# Busboard_expand_v12.net
KiCad netlist of a schematic drawn in EAGLE
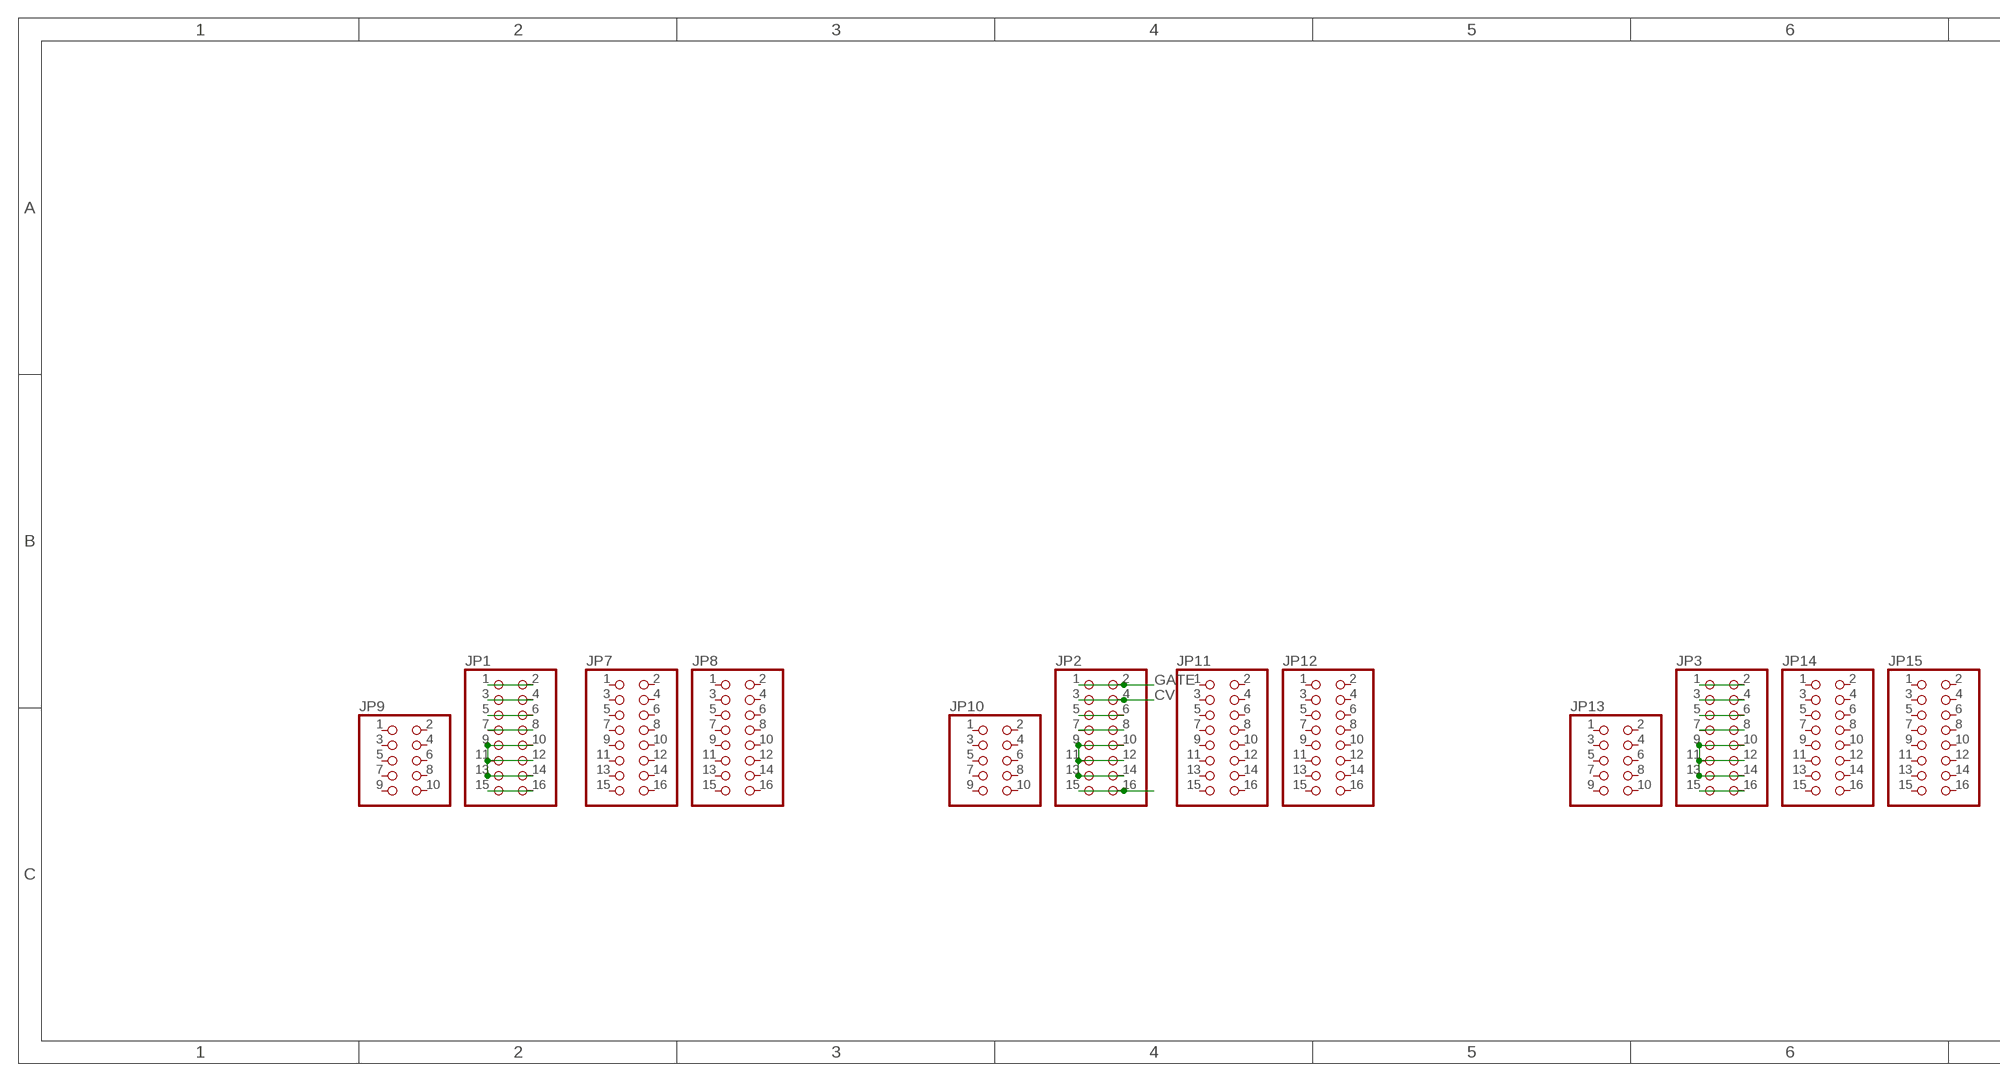
[diagram p0: schematic, sheet 1, part 1 of 2]
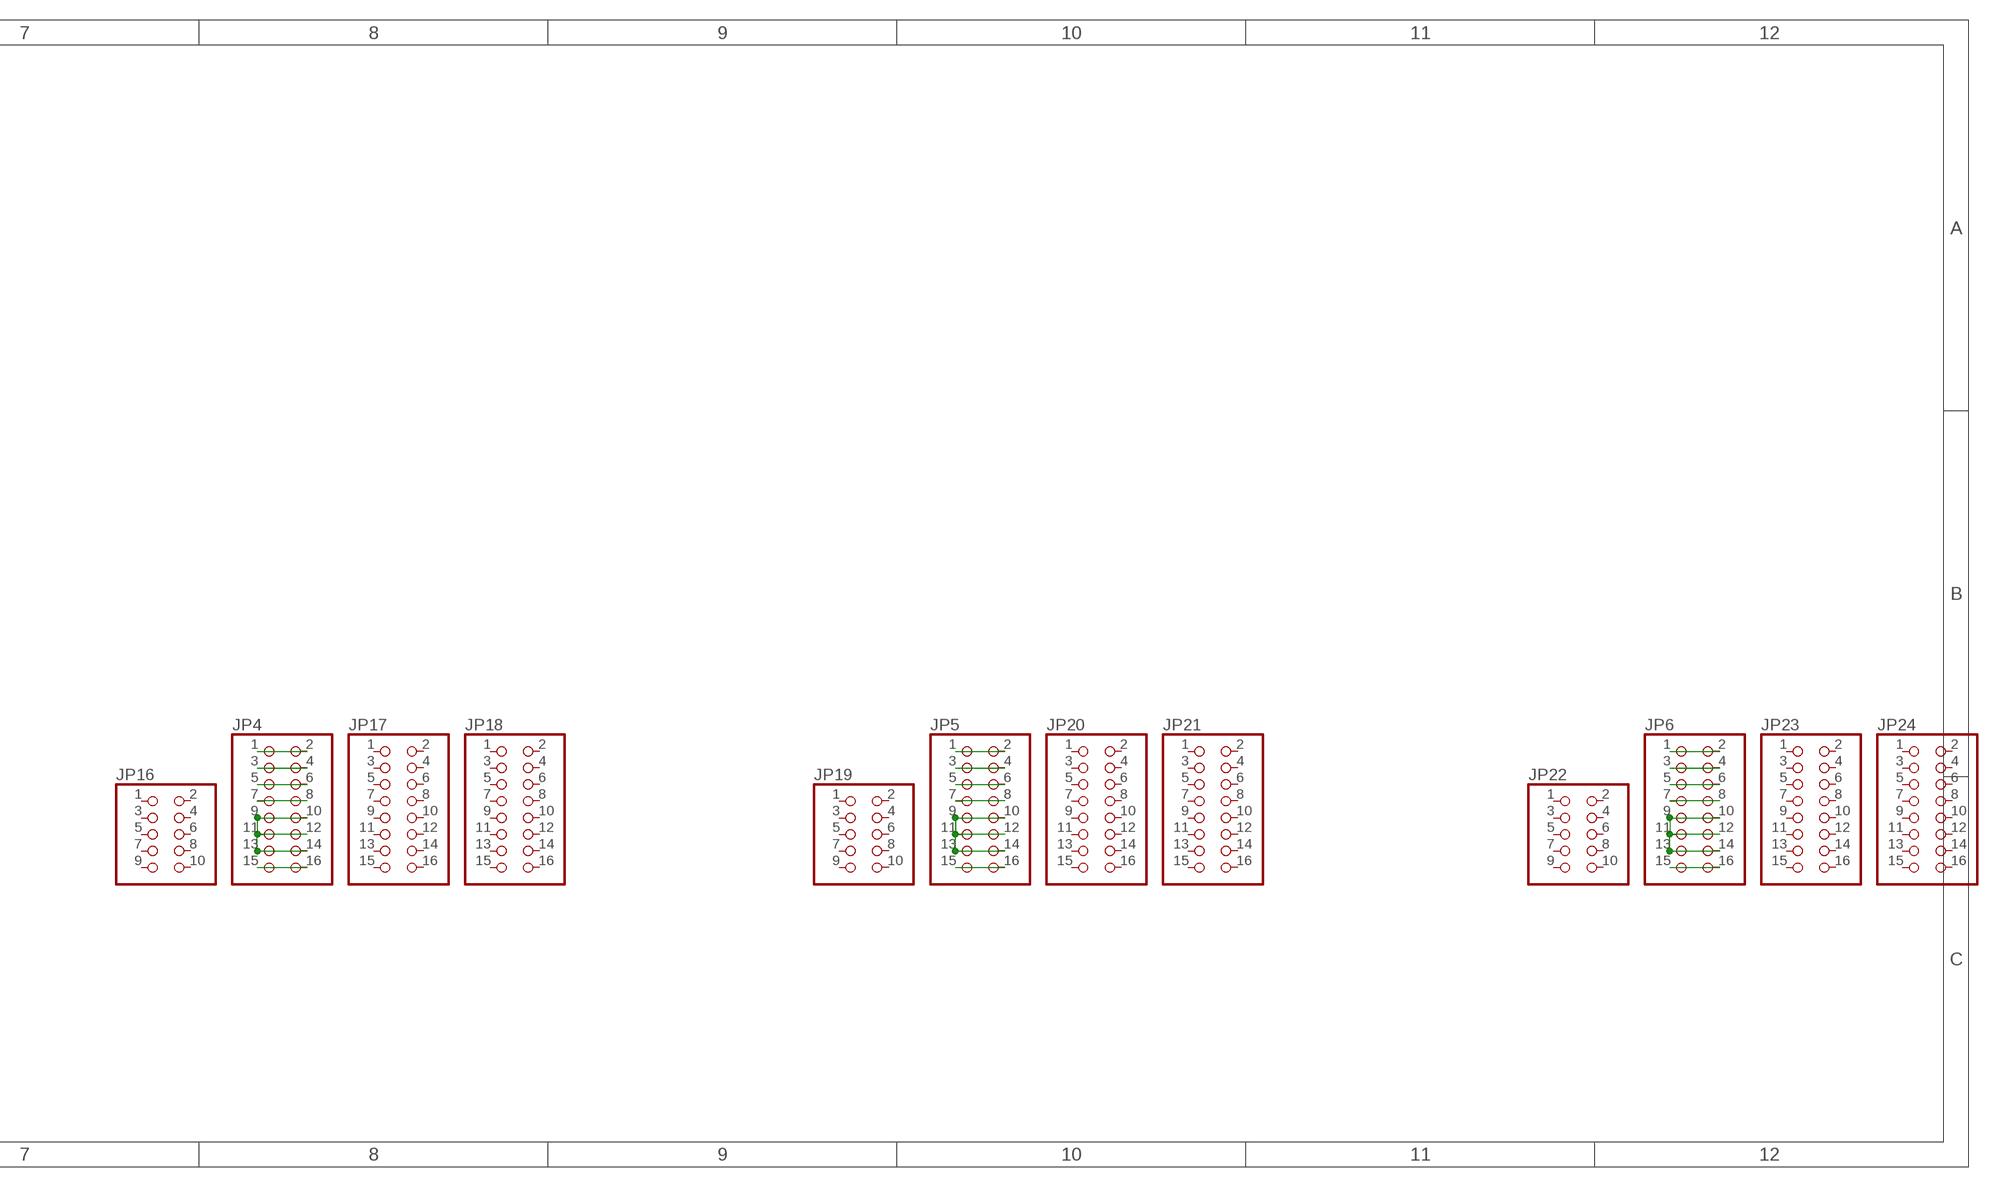
[diagram p1: schematic, sheet 1, part 2 of 2]

(export (version "E")
  (design (tool "Eeschema 10.0.6"))
  (components
    (comp (ref "JP1")
      (value "PINHD-2X8")
      (footprint "eagle-import:2X08")
      (libsource (lib "eagle-import") (part "PINHD-2X8"))
    )
    (comp (ref "JP2")
      (value "PINHD-2X8")
      (footprint "eagle-import:2X08")
      (libsource (lib "eagle-import") (part "PINHD-2X8"))
    )
    (comp (ref "JP3")
      (value "PINHD-2X8")
      (footprint "eagle-import:2X08")
      (libsource (lib "eagle-import") (part "PINHD-2X8"))
    )
    (comp (ref "JP4")
      (value "PINHD-2X8")
      (footprint "eagle-import:2X08")
      (libsource (lib "eagle-import") (part "PINHD-2X8"))
    )
    (comp (ref "JP5")
      (value "PINHD-2X8")
      (footprint "eagle-import:2X08")
      (libsource (lib "eagle-import") (part "PINHD-2X8"))
    )
    (comp (ref "JP6")
      (value "PINHD-2X8")
      (footprint "eagle-import:2X08")
      (libsource (lib "eagle-import") (part "PINHD-2X8"))
    )
    (comp (ref "JP7")
      (value "PINHD-2X8/90")
      (footprint "eagle-import:2X08_90")
      (libsource (lib "eagle-import") (part "pinhead_325_PINHD-2X8/90"))
    )
    (comp (ref "JP8")
      (value "PINHD-2X8/90")
      (footprint "eagle-import:2X08_90")
      (libsource (lib "eagle-import") (part "pinhead_325_PINHD-2X8/90"))
    )
    (comp (ref "JP9")
      (value "PINHD-2X5")
      (footprint "eagle-import:2X05")
      (libsource (lib "eagle-import") (part "PINHD-2X5"))
    )
    (comp (ref "JP10")
      (value "PINHD-2X5")
      (footprint "eagle-import:2X05")
      (libsource (lib "eagle-import") (part "PINHD-2X5"))
    )
    (comp (ref "JP11")
      (value "PINHD-2X8/90")
      (footprint "eagle-import:2X08_90")
      (libsource (lib "eagle-import") (part "pinhead_325_PINHD-2X8/90"))
    )
    (comp (ref "JP12")
      (value "PINHD-2X8/90")
      (footprint "eagle-import:2X08_90")
      (libsource (lib "eagle-import") (part "pinhead_325_PINHD-2X8/90"))
    )
    (comp (ref "JP13")
      (value "PINHD-2X5")
      (footprint "eagle-import:2X05")
      (libsource (lib "eagle-import") (part "PINHD-2X5"))
    )
    (comp (ref "JP14")
      (value "PINHD-2X8/90")
      (footprint "eagle-import:2X08_90")
      (libsource (lib "eagle-import") (part "pinhead_325_PINHD-2X8/90"))
    )
    (comp (ref "JP15")
      (value "PINHD-2X8/90")
      (footprint "eagle-import:2X08_90")
      (libsource (lib "eagle-import") (part "pinhead_325_PINHD-2X8/90"))
    )
    (comp (ref "JP16")
      (value "PINHD-2X5")
      (footprint "eagle-import:2X05")
      (libsource (lib "eagle-import") (part "PINHD-2X5"))
    )
    (comp (ref "JP17")
      (value "PINHD-2X8/90")
      (footprint "eagle-import:2X08_90")
      (libsource (lib "eagle-import") (part "pinhead_325_PINHD-2X8/90"))
    )
    (comp (ref "JP18")
      (value "PINHD-2X8/90")
      (footprint "eagle-import:2X08_90")
      (libsource (lib "eagle-import") (part "pinhead_325_PINHD-2X8/90"))
    )
    (comp (ref "JP19")
      (value "PINHD-2X5")
      (footprint "eagle-import:2X05")
      (libsource (lib "eagle-import") (part "PINHD-2X5"))
    )
    (comp (ref "JP20")
      (value "PINHD-2X8/90")
      (footprint "eagle-import:2X08_90")
      (libsource (lib "eagle-import") (part "pinhead_325_PINHD-2X8/90"))
    )
    (comp (ref "JP21")
      (value "PINHD-2X8/90")
      (footprint "eagle-import:2X08_90")
      (libsource (lib "eagle-import") (part "pinhead_325_PINHD-2X8/90"))
    )
    (comp (ref "JP22")
      (value "PINHD-2X5")
      (footprint "eagle-import:2X05")
      (libsource (lib "eagle-import") (part "PINHD-2X5"))
    )
    (comp (ref "JP23")
      (value "PINHD-2X8/90")
      (footprint "eagle-import:2X08_90")
      (libsource (lib "eagle-import") (part "pinhead_325_PINHD-2X8/90"))
    )
    (comp (ref "JP24")
      (value "PINHD-2X8/90")
      (footprint "eagle-import:2X08_90")
      (libsource (lib "eagle-import") (part "pinhead_325_PINHD-2X8/90"))
    )
  )
  (nets
    (net (code "1") (name "/CV") (class "Default")
      (node (ref "JP1") (pin "3") (pinfunction "3_3") (pintype "passive"))
      (node (ref "JP1") (pin "4") (pinfunction "4_4") (pintype "passive"))
      (node (ref "JP2") (pin "3") (pinfunction "3_3") (pintype "passive"))
      (node (ref "JP2") (pin "4") (pinfunction "4_4") (pintype "passive"))
      (node (ref "JP3") (pin "3") (pinfunction "3_3") (pintype "passive"))
      (node (ref "JP3") (pin "4") (pinfunction "4_4") (pintype "passive"))
      (node (ref "JP4") (pin "3") (pinfunction "3_3") (pintype "passive"))
      (node (ref "JP4") (pin "4") (pinfunction "4_4") (pintype "passive"))
      (node (ref "JP5") (pin "3") (pinfunction "3_3") (pintype "passive"))
      (node (ref "JP5") (pin "4") (pinfunction "4_4") (pintype "passive"))
      (node (ref "JP6") (pin "3") (pinfunction "3_3") (pintype "passive"))
      (node (ref "JP6") (pin "4") (pinfunction "4_4") (pintype "passive"))
    )
    (net (code "2") (name "/GATE") (class "Default")
      (node (ref "JP1") (pin "1") (pinfunction "1_1") (pintype "passive"))
      (node (ref "JP1") (pin "2") (pinfunction "2_2") (pintype "passive"))
      (node (ref "JP2") (pin "1") (pinfunction "1_1") (pintype "passive"))
      (node (ref "JP2") (pin "2") (pinfunction "2_2") (pintype "passive"))
      (node (ref "JP3") (pin "1") (pinfunction "1_1") (pintype "passive"))
      (node (ref "JP3") (pin "2") (pinfunction "2_2") (pintype "passive"))
      (node (ref "JP4") (pin "1") (pinfunction "1_1") (pintype "passive"))
      (node (ref "JP4") (pin "2") (pinfunction "2_2") (pintype "passive"))
      (node (ref "JP5") (pin "1") (pinfunction "1_1") (pintype "passive"))
      (node (ref "JP5") (pin "2") (pinfunction "2_2") (pintype "passive"))
      (node (ref "JP6") (pin "1") (pinfunction "1_1") (pintype "passive"))
      (node (ref "JP6") (pin "2") (pinfunction "2_2") (pintype "passive"))
    )
    (net (code "3") (name "Net-(JP1-Pad5)") (class "Default")
      (node (ref "JP1") (pin "5") (pinfunction "5_5") (pintype "passive"))
      (node (ref "JP1") (pin "6") (pinfunction "6_6") (pintype "passive"))
    )
    (net (code "4") (name "Net-(JP1-Pad7)") (class "Default")
      (node (ref "JP1") (pin "7") (pinfunction "7_7") (pintype "passive"))
      (node (ref "JP1") (pin "8") (pinfunction "8_8") (pintype "passive"))
    )
    (net (code "5") (name "Net-(JP1-Pad10)") (class "Default")
      (node (ref "JP1") (pin "10") (pinfunction "10_10") (pintype "passive"))
      (node (ref "JP1") (pin "11") (pinfunction "11_11") (pintype "passive"))
      (node (ref "JP1") (pin "12") (pinfunction "12_12") (pintype "passive"))
      (node (ref "JP1") (pin "13") (pinfunction "13_13") (pintype "passive"))
      (node (ref "JP1") (pin "14") (pinfunction "14_14") (pintype "passive"))
      (node (ref "JP1") (pin "9") (pinfunction "9_9") (pintype "passive"))
    )
    (net (code "6") (name "Net-(JP1-Pad15)") (class "Default")
      (node (ref "JP1") (pin "15") (pinfunction "15_15") (pintype "passive"))
      (node (ref "JP1") (pin "16") (pinfunction "16_16") (pintype "passive"))
    )
    (net (code "7") (name "Net-(JP2-Pad5)") (class "Default")
      (node (ref "JP2") (pin "5") (pinfunction "5_5") (pintype "passive"))
      (node (ref "JP2") (pin "6") (pinfunction "6_6") (pintype "passive"))
    )
    (net (code "8") (name "Net-(JP2-Pad7)") (class "Default")
      (node (ref "JP2") (pin "7") (pinfunction "7_7") (pintype "passive"))
      (node (ref "JP2") (pin "8") (pinfunction "8_8") (pintype "passive"))
    )
    (net (code "9") (name "Net-(JP2-Pad10)") (class "Default")
      (node (ref "JP2") (pin "10") (pinfunction "10_10") (pintype "passive"))
      (node (ref "JP2") (pin "11") (pinfunction "11_11") (pintype "passive"))
      (node (ref "JP2") (pin "12") (pinfunction "12_12") (pintype "passive"))
      (node (ref "JP2") (pin "13") (pinfunction "13_13") (pintype "passive"))
      (node (ref "JP2") (pin "14") (pinfunction "14_14") (pintype "passive"))
      (node (ref "JP2") (pin "9") (pinfunction "9_9") (pintype "passive"))
    )
    (net (code "10") (name "Net-(JP2-Pad15)") (class "Default")
      (node (ref "JP2") (pin "15") (pinfunction "15_15") (pintype "passive"))
      (node (ref "JP2") (pin "16") (pinfunction "16_16") (pintype "passive"))
    )
    (net (code "11") (name "Net-(JP3-Pad5)") (class "Default")
      (node (ref "JP3") (pin "5") (pinfunction "5_5") (pintype "passive"))
      (node (ref "JP3") (pin "6") (pinfunction "6_6") (pintype "passive"))
    )
    (net (code "12") (name "Net-(JP3-Pad7)") (class "Default")
      (node (ref "JP3") (pin "7") (pinfunction "7_7") (pintype "passive"))
      (node (ref "JP3") (pin "8") (pinfunction "8_8") (pintype "passive"))
    )
    (net (code "13") (name "Net-(JP3-Pad10)") (class "Default")
      (node (ref "JP3") (pin "10") (pinfunction "10_10") (pintype "passive"))
      (node (ref "JP3") (pin "11") (pinfunction "11_11") (pintype "passive"))
      (node (ref "JP3") (pin "12") (pinfunction "12_12") (pintype "passive"))
      (node (ref "JP3") (pin "13") (pinfunction "13_13") (pintype "passive"))
      (node (ref "JP3") (pin "14") (pinfunction "14_14") (pintype "passive"))
      (node (ref "JP3") (pin "9") (pinfunction "9_9") (pintype "passive"))
    )
    (net (code "14") (name "Net-(JP3-Pad15)") (class "Default")
      (node (ref "JP3") (pin "15") (pinfunction "15_15") (pintype "passive"))
      (node (ref "JP3") (pin "16") (pinfunction "16_16") (pintype "passive"))
    )
    (net (code "15") (name "Net-(JP4-Pad5)") (class "Default")
      (node (ref "JP4") (pin "5") (pinfunction "5_5") (pintype "passive"))
      (node (ref "JP4") (pin "6") (pinfunction "6_6") (pintype "passive"))
    )
    (net (code "16") (name "Net-(JP4-Pad7)") (class "Default")
      (node (ref "JP4") (pin "7") (pinfunction "7_7") (pintype "passive"))
      (node (ref "JP4") (pin "8") (pinfunction "8_8") (pintype "passive"))
    )
    (net (code "17") (name "Net-(JP4-Pad10)") (class "Default")
      (node (ref "JP4") (pin "10") (pinfunction "10_10") (pintype "passive"))
      (node (ref "JP4") (pin "11") (pinfunction "11_11") (pintype "passive"))
      (node (ref "JP4") (pin "12") (pinfunction "12_12") (pintype "passive"))
      (node (ref "JP4") (pin "13") (pinfunction "13_13") (pintype "passive"))
      (node (ref "JP4") (pin "14") (pinfunction "14_14") (pintype "passive"))
      (node (ref "JP4") (pin "9") (pinfunction "9_9") (pintype "passive"))
    )
    (net (code "18") (name "Net-(JP4-Pad15)") (class "Default")
      (node (ref "JP4") (pin "15") (pinfunction "15_15") (pintype "passive"))
      (node (ref "JP4") (pin "16") (pinfunction "16_16") (pintype "passive"))
    )
    (net (code "19") (name "Net-(JP5-Pad5)") (class "Default")
      (node (ref "JP5") (pin "5") (pinfunction "5_5") (pintype "passive"))
      (node (ref "JP5") (pin "6") (pinfunction "6_6") (pintype "passive"))
    )
    (net (code "20") (name "Net-(JP5-Pad7)") (class "Default")
      (node (ref "JP5") (pin "7") (pinfunction "7_7") (pintype "passive"))
      (node (ref "JP5") (pin "8") (pinfunction "8_8") (pintype "passive"))
    )
    (net (code "21") (name "Net-(JP5-Pad10)") (class "Default")
      (node (ref "JP5") (pin "10") (pinfunction "10_10") (pintype "passive"))
      (node (ref "JP5") (pin "11") (pinfunction "11_11") (pintype "passive"))
      (node (ref "JP5") (pin "12") (pinfunction "12_12") (pintype "passive"))
      (node (ref "JP5") (pin "13") (pinfunction "13_13") (pintype "passive"))
      (node (ref "JP5") (pin "14") (pinfunction "14_14") (pintype "passive"))
      (node (ref "JP5") (pin "9") (pinfunction "9_9") (pintype "passive"))
    )
    (net (code "22") (name "Net-(JP5-Pad15)") (class "Default")
      (node (ref "JP5") (pin "15") (pinfunction "15_15") (pintype "passive"))
      (node (ref "JP5") (pin "16") (pinfunction "16_16") (pintype "passive"))
    )
    (net (code "23") (name "Net-(JP6-Pad5)") (class "Default")
      (node (ref "JP6") (pin "5") (pinfunction "5_5") (pintype "passive"))
      (node (ref "JP6") (pin "6") (pinfunction "6_6") (pintype "passive"))
    )
    (net (code "24") (name "Net-(JP6-Pad7)") (class "Default")
      (node (ref "JP6") (pin "7") (pinfunction "7_7") (pintype "passive"))
      (node (ref "JP6") (pin "8") (pinfunction "8_8") (pintype "passive"))
    )
    (net (code "25") (name "Net-(JP6-Pad10)") (class "Default")
      (node (ref "JP6") (pin "10") (pinfunction "10_10") (pintype "passive"))
      (node (ref "JP6") (pin "11") (pinfunction "11_11") (pintype "passive"))
      (node (ref "JP6") (pin "12") (pinfunction "12_12") (pintype "passive"))
      (node (ref "JP6") (pin "13") (pinfunction "13_13") (pintype "passive"))
      (node (ref "JP6") (pin "14") (pinfunction "14_14") (pintype "passive"))
      (node (ref "JP6") (pin "9") (pinfunction "9_9") (pintype "passive"))
    )
    (net (code "26") (name "Net-(JP6-Pad15)") (class "Default")
      (node (ref "JP6") (pin "15") (pinfunction "15_15") (pintype "passive"))
      (node (ref "JP6") (pin "16") (pinfunction "16_16") (pintype "passive"))
    )
    (net (code "27") (name "unconnected-(JP7-Pad1)") (class "Default")
      (node (ref "JP7") (pin "1") (pinfunction "1_1") (pintype "passive"))
    )
    (net (code "28") (name "unconnected-(JP7-Pad2)") (class "Default")
      (node (ref "JP7") (pin "2") (pinfunction "2_2") (pintype "passive"))
    )
    (net (code "29") (name "unconnected-(JP7-Pad3)") (class "Default")
      (node (ref "JP7") (pin "3") (pinfunction "3_3") (pintype "passive"))
    )
    (net (code "30") (name "unconnected-(JP7-Pad4)") (class "Default")
      (node (ref "JP7") (pin "4") (pinfunction "4_4") (pintype "passive"))
    )
    (net (code "31") (name "unconnected-(JP7-Pad5)") (class "Default")
      (node (ref "JP7") (pin "5") (pinfunction "5_5") (pintype "passive"))
    )
    (net (code "32") (name "unconnected-(JP7-Pad6)") (class "Default")
      (node (ref "JP7") (pin "6") (pinfunction "6_6") (pintype "passive"))
    )
    (net (code "33") (name "unconnected-(JP7-Pad7)") (class "Default")
      (node (ref "JP7") (pin "7") (pinfunction "7_7") (pintype "passive"))
    )
    (net (code "34") (name "unconnected-(JP7-Pad8)") (class "Default")
      (node (ref "JP7") (pin "8") (pinfunction "8_8") (pintype "passive"))
    )
    (net (code "35") (name "unconnected-(JP7-Pad9)") (class "Default")
      (node (ref "JP7") (pin "9") (pinfunction "9_9") (pintype "passive"))
    )
    (net (code "36") (name "unconnected-(JP7-Pad10)") (class "Default")
      (node (ref "JP7") (pin "10") (pinfunction "10_10") (pintype "passive"))
    )
    (net (code "37") (name "unconnected-(JP7-Pad11)") (class "Default")
      (node (ref "JP7") (pin "11") (pinfunction "11_11") (pintype "passive"))
    )
    (net (code "38") (name "unconnected-(JP7-Pad12)") (class "Default")
      (node (ref "JP7") (pin "12") (pinfunction "12_12") (pintype "passive"))
    )
    (net (code "39") (name "unconnected-(JP7-Pad13)") (class "Default")
      (node (ref "JP7") (pin "13") (pinfunction "13_13") (pintype "passive"))
    )
    (net (code "40") (name "unconnected-(JP7-Pad14)") (class "Default")
      (node (ref "JP7") (pin "14") (pinfunction "14_14") (pintype "passive"))
    )
    (net (code "41") (name "unconnected-(JP7-Pad15)") (class "Default")
      (node (ref "JP7") (pin "15") (pinfunction "15_15") (pintype "passive"))
    )
    (net (code "42") (name "unconnected-(JP7-Pad16)") (class "Default")
      (node (ref "JP7") (pin "16") (pinfunction "16_16") (pintype "passive"))
    )
    (net (code "43") (name "unconnected-(JP8-Pad1)") (class "Default")
      (node (ref "JP8") (pin "1") (pinfunction "1_1") (pintype "passive"))
    )
    (net (code "44") (name "unconnected-(JP8-Pad2)") (class "Default")
      (node (ref "JP8") (pin "2") (pinfunction "2_2") (pintype "passive"))
    )
    (net (code "45") (name "unconnected-(JP8-Pad3)") (class "Default")
      (node (ref "JP8") (pin "3") (pinfunction "3_3") (pintype "passive"))
    )
    (net (code "46") (name "unconnected-(JP8-Pad4)") (class "Default")
      (node (ref "JP8") (pin "4") (pinfunction "4_4") (pintype "passive"))
    )
    (net (code "47") (name "unconnected-(JP8-Pad5)") (class "Default")
      (node (ref "JP8") (pin "5") (pinfunction "5_5") (pintype "passive"))
    )
    (net (code "48") (name "unconnected-(JP8-Pad6)") (class "Default")
      (node (ref "JP8") (pin "6") (pinfunction "6_6") (pintype "passive"))
    )
    (net (code "49") (name "unconnected-(JP8-Pad7)") (class "Default")
      (node (ref "JP8") (pin "7") (pinfunction "7_7") (pintype "passive"))
    )
    (net (code "50") (name "unconnected-(JP8-Pad8)") (class "Default")
      (node (ref "JP8") (pin "8") (pinfunction "8_8") (pintype "passive"))
    )
    (net (code "51") (name "unconnected-(JP8-Pad9)") (class "Default")
      (node (ref "JP8") (pin "9") (pinfunction "9_9") (pintype "passive"))
    )
    (net (code "52") (name "unconnected-(JP8-Pad10)") (class "Default")
      (node (ref "JP8") (pin "10") (pinfunction "10_10") (pintype "passive"))
    )
    (net (code "53") (name "unconnected-(JP8-Pad11)") (class "Default")
      (node (ref "JP8") (pin "11") (pinfunction "11_11") (pintype "passive"))
    )
    (net (code "54") (name "unconnected-(JP8-Pad12)") (class "Default")
      (node (ref "JP8") (pin "12") (pinfunction "12_12") (pintype "passive"))
    )
    (net (code "55") (name "unconnected-(JP8-Pad13)") (class "Default")
      (node (ref "JP8") (pin "13") (pinfunction "13_13") (pintype "passive"))
    )
    (net (code "56") (name "unconnected-(JP8-Pad14)") (class "Default")
      (node (ref "JP8") (pin "14") (pinfunction "14_14") (pintype "passive"))
    )
    (net (code "57") (name "unconnected-(JP8-Pad15)") (class "Default")
      (node (ref "JP8") (pin "15") (pinfunction "15_15") (pintype "passive"))
    )
    (net (code "58") (name "unconnected-(JP8-Pad16)") (class "Default")
      (node (ref "JP8") (pin "16") (pinfunction "16_16") (pintype "passive"))
    )
    (net (code "59") (name "unconnected-(JP9-Pad1)") (class "Default")
      (node (ref "JP9") (pin "1") (pinfunction "1_1") (pintype "passive"))
    )
    (net (code "60") (name "unconnected-(JP9-Pad2)") (class "Default")
      (node (ref "JP9") (pin "2") (pinfunction "2_2") (pintype "passive"))
    )
    (net (code "61") (name "unconnected-(JP9-Pad3)") (class "Default")
      (node (ref "JP9") (pin "3") (pinfunction "3_3") (pintype "passive"))
    )
    (net (code "62") (name "unconnected-(JP9-Pad4)") (class "Default")
      (node (ref "JP9") (pin "4") (pinfunction "4_4") (pintype "passive"))
    )
    (net (code "63") (name "unconnected-(JP9-Pad5)") (class "Default")
      (node (ref "JP9") (pin "5") (pinfunction "5_5") (pintype "passive"))
    )
    (net (code "64") (name "unconnected-(JP9-Pad6)") (class "Default")
      (node (ref "JP9") (pin "6") (pinfunction "6_6") (pintype "passive"))
    )
    (net (code "65") (name "unconnected-(JP9-Pad7)") (class "Default")
      (node (ref "JP9") (pin "7") (pinfunction "7_7") (pintype "passive"))
    )
    (net (code "66") (name "unconnected-(JP9-Pad8)") (class "Default")
      (node (ref "JP9") (pin "8") (pinfunction "8_8") (pintype "passive"))
    )
    (net (code "67") (name "unconnected-(JP9-Pad9)") (class "Default")
      (node (ref "JP9") (pin "9") (pinfunction "9_9") (pintype "passive"))
    )
    (net (code "68") (name "unconnected-(JP9-Pad10)") (class "Default")
      (node (ref "JP9") (pin "10") (pinfunction "10_10") (pintype "passive"))
    )
    (net (code "69") (name "unconnected-(JP10-Pad1)") (class "Default")
      (node (ref "JP10") (pin "1") (pinfunction "1_1") (pintype "passive"))
    )
    (net (code "70") (name "unconnected-(JP10-Pad2)") (class "Default")
      (node (ref "JP10") (pin "2") (pinfunction "2_2") (pintype "passive"))
    )
    (net (code "71") (name "unconnected-(JP10-Pad3)") (class "Default")
      (node (ref "JP10") (pin "3") (pinfunction "3_3") (pintype "passive"))
    )
    (net (code "72") (name "unconnected-(JP10-Pad4)") (class "Default")
      (node (ref "JP10") (pin "4") (pinfunction "4_4") (pintype "passive"))
    )
    (net (code "73") (name "unconnected-(JP10-Pad5)") (class "Default")
      (node (ref "JP10") (pin "5") (pinfunction "5_5") (pintype "passive"))
    )
    (net (code "74") (name "unconnected-(JP10-Pad6)") (class "Default")
      (node (ref "JP10") (pin "6") (pinfunction "6_6") (pintype "passive"))
    )
    (net (code "75") (name "unconnected-(JP10-Pad7)") (class "Default")
      (node (ref "JP10") (pin "7") (pinfunction "7_7") (pintype "passive"))
    )
    (net (code "76") (name "unconnected-(JP10-Pad8)") (class "Default")
      (node (ref "JP10") (pin "8") (pinfunction "8_8") (pintype "passive"))
    )
    (net (code "77") (name "unconnected-(JP10-Pad9)") (class "Default")
      (node (ref "JP10") (pin "9") (pinfunction "9_9") (pintype "passive"))
    )
    (net (code "78") (name "unconnected-(JP10-Pad10)") (class "Default")
      (node (ref "JP10") (pin "10") (pinfunction "10_10") (pintype "passive"))
    )
    (net (code "79") (name "unconnected-(JP11-Pad1)") (class "Default")
      (node (ref "JP11") (pin "1") (pinfunction "1_1") (pintype "passive"))
    )
    (net (code "80") (name "unconnected-(JP11-Pad2)") (class "Default")
      (node (ref "JP11") (pin "2") (pinfunction "2_2") (pintype "passive"))
    )
    (net (code "81") (name "unconnected-(JP11-Pad3)") (class "Default")
      (node (ref "JP11") (pin "3") (pinfunction "3_3") (pintype "passive"))
    )
    (net (code "82") (name "unconnected-(JP11-Pad4)") (class "Default")
      (node (ref "JP11") (pin "4") (pinfunction "4_4") (pintype "passive"))
    )
    (net (code "83") (name "unconnected-(JP11-Pad5)") (class "Default")
      (node (ref "JP11") (pin "5") (pinfunction "5_5") (pintype "passive"))
    )
    (net (code "84") (name "unconnected-(JP11-Pad6)") (class "Default")
      (node (ref "JP11") (pin "6") (pinfunction "6_6") (pintype "passive"))
    )
    (net (code "85") (name "unconnected-(JP11-Pad7)") (class "Default")
      (node (ref "JP11") (pin "7") (pinfunction "7_7") (pintype "passive"))
    )
    (net (code "86") (name "unconnected-(JP11-Pad8)") (class "Default")
      (node (ref "JP11") (pin "8") (pinfunction "8_8") (pintype "passive"))
    )
    (net (code "87") (name "unconnected-(JP11-Pad9)") (class "Default")
      (node (ref "JP11") (pin "9") (pinfunction "9_9") (pintype "passive"))
    )
    (net (code "88") (name "unconnected-(JP11-Pad10)") (class "Default")
      (node (ref "JP11") (pin "10") (pinfunction "10_10") (pintype "passive"))
    )
    (net (code "89") (name "unconnected-(JP11-Pad11)") (class "Default")
      (node (ref "JP11") (pin "11") (pinfunction "11_11") (pintype "passive"))
    )
    (net (code "90") (name "unconnected-(JP11-Pad12)") (class "Default")
      (node (ref "JP11") (pin "12") (pinfunction "12_12") (pintype "passive"))
    )
    (net (code "91") (name "unconnected-(JP11-Pad13)") (class "Default")
      (node (ref "JP11") (pin "13") (pinfunction "13_13") (pintype "passive"))
    )
    (net (code "92") (name "unconnected-(JP11-Pad14)") (class "Default")
      (node (ref "JP11") (pin "14") (pinfunction "14_14") (pintype "passive"))
    )
    (net (code "93") (name "unconnected-(JP11-Pad15)") (class "Default")
      (node (ref "JP11") (pin "15") (pinfunction "15_15") (pintype "passive"))
    )
    (net (code "94") (name "unconnected-(JP11-Pad16)") (class "Default")
      (node (ref "JP11") (pin "16") (pinfunction "16_16") (pintype "passive"))
    )
    (net (code "95") (name "unconnected-(JP12-Pad1)") (class "Default")
      (node (ref "JP12") (pin "1") (pinfunction "1_1") (pintype "passive"))
    )
    (net (code "96") (name "unconnected-(JP12-Pad2)") (class "Default")
      (node (ref "JP12") (pin "2") (pinfunction "2_2") (pintype "passive"))
    )
    (net (code "97") (name "unconnected-(JP12-Pad3)") (class "Default")
      (node (ref "JP12") (pin "3") (pinfunction "3_3") (pintype "passive"))
    )
    (net (code "98") (name "unconnected-(JP12-Pad4)") (class "Default")
      (node (ref "JP12") (pin "4") (pinfunction "4_4") (pintype "passive"))
    )
    (net (code "99") (name "unconnected-(JP12-Pad5)") (class "Default")
      (node (ref "JP12") (pin "5") (pinfunction "5_5") (pintype "passive"))
    )
    (net (code "100") (name "unconnected-(JP12-Pad6)") (class "Default")
      (node (ref "JP12") (pin "6") (pinfunction "6_6") (pintype "passive"))
    )
    (net (code "101") (name "unconnected-(JP12-Pad7)") (class "Default")
      (node (ref "JP12") (pin "7") (pinfunction "7_7") (pintype "passive"))
    )
    (net (code "102") (name "unconnected-(JP12-Pad8)") (class "Default")
      (node (ref "JP12") (pin "8") (pinfunction "8_8") (pintype "passive"))
    )
    (net (code "103") (name "unconnected-(JP12-Pad9)") (class "Default")
      (node (ref "JP12") (pin "9") (pinfunction "9_9") (pintype "passive"))
    )
    (net (code "104") (name "unconnected-(JP12-Pad10)") (class "Default")
      (node (ref "JP12") (pin "10") (pinfunction "10_10") (pintype "passive"))
    )
    (net (code "105") (name "unconnected-(JP12-Pad11)") (class "Default")
      (node (ref "JP12") (pin "11") (pinfunction "11_11") (pintype "passive"))
    )
    (net (code "106") (name "unconnected-(JP12-Pad12)") (class "Default")
      (node (ref "JP12") (pin "12") (pinfunction "12_12") (pintype "passive"))
    )
    (net (code "107") (name "unconnected-(JP12-Pad13)") (class "Default")
      (node (ref "JP12") (pin "13") (pinfunction "13_13") (pintype "passive"))
    )
    (net (code "108") (name "unconnected-(JP12-Pad14)") (class "Default")
      (node (ref "JP12") (pin "14") (pinfunction "14_14") (pintype "passive"))
    )
    (net (code "109") (name "unconnected-(JP12-Pad15)") (class "Default")
      (node (ref "JP12") (pin "15") (pinfunction "15_15") (pintype "passive"))
    )
    (net (code "110") (name "unconnected-(JP12-Pad16)") (class "Default")
      (node (ref "JP12") (pin "16") (pinfunction "16_16") (pintype "passive"))
    )
    (net (code "111") (name "unconnected-(JP13-Pad1)") (class "Default")
      (node (ref "JP13") (pin "1") (pinfunction "1_1") (pintype "passive"))
    )
    (net (code "112") (name "unconnected-(JP13-Pad2)") (class "Default")
      (node (ref "JP13") (pin "2") (pinfunction "2_2") (pintype "passive"))
    )
    (net (code "113") (name "unconnected-(JP13-Pad3)") (class "Default")
      (node (ref "JP13") (pin "3") (pinfunction "3_3") (pintype "passive"))
    )
    (net (code "114") (name "unconnected-(JP13-Pad4)") (class "Default")
      (node (ref "JP13") (pin "4") (pinfunction "4_4") (pintype "passive"))
    )
    (net (code "115") (name "unconnected-(JP13-Pad5)") (class "Default")
      (node (ref "JP13") (pin "5") (pinfunction "5_5") (pintype "passive"))
    )
    (net (code "116") (name "unconnected-(JP13-Pad6)") (class "Default")
      (node (ref "JP13") (pin "6") (pinfunction "6_6") (pintype "passive"))
    )
    (net (code "117") (name "unconnected-(JP13-Pad7)") (class "Default")
      (node (ref "JP13") (pin "7") (pinfunction "7_7") (pintype "passive"))
    )
    (net (code "118") (name "unconnected-(JP13-Pad8)") (class "Default")
      (node (ref "JP13") (pin "8") (pinfunction "8_8") (pintype "passive"))
    )
    (net (code "119") (name "unconnected-(JP13-Pad9)") (class "Default")
      (node (ref "JP13") (pin "9") (pinfunction "9_9") (pintype "passive"))
    )
    (net (code "120") (name "unconnected-(JP13-Pad10)") (class "Default")
      (node (ref "JP13") (pin "10") (pinfunction "10_10") (pintype "passive"))
    )
    (net (code "121") (name "unconnected-(JP14-Pad1)") (class "Default")
      (node (ref "JP14") (pin "1") (pinfunction "1_1") (pintype "passive"))
    )
    (net (code "122") (name "unconnected-(JP14-Pad2)") (class "Default")
      (node (ref "JP14") (pin "2") (pinfunction "2_2") (pintype "passive"))
    )
    (net (code "123") (name "unconnected-(JP14-Pad3)") (class "Default")
      (node (ref "JP14") (pin "3") (pinfunction "3_3") (pintype "passive"))
    )
    (net (code "124") (name "unconnected-(JP14-Pad4)") (class "Default")
      (node (ref "JP14") (pin "4") (pinfunction "4_4") (pintype "passive"))
    )
    (net (code "125") (name "unconnected-(JP14-Pad5)") (class "Default")
      (node (ref "JP14") (pin "5") (pinfunction "5_5") (pintype "passive"))
    )
    (net (code "126") (name "unconnected-(JP14-Pad6)") (class "Default")
      (node (ref "JP14") (pin "6") (pinfunction "6_6") (pintype "passive"))
    )
    (net (code "127") (name "unconnected-(JP14-Pad7)") (class "Default")
      (node (ref "JP14") (pin "7") (pinfunction "7_7") (pintype "passive"))
    )
    (net (code "128") (name "unconnected-(JP14-Pad8)") (class "Default")
      (node (ref "JP14") (pin "8") (pinfunction "8_8") (pintype "passive"))
    )
    (net (code "129") (name "unconnected-(JP14-Pad9)") (class "Default")
      (node (ref "JP14") (pin "9") (pinfunction "9_9") (pintype "passive"))
    )
    (net (code "130") (name "unconnected-(JP14-Pad10)") (class "Default")
      (node (ref "JP14") (pin "10") (pinfunction "10_10") (pintype "passive"))
    )
    (net (code "131") (name "unconnected-(JP14-Pad11)") (class "Default")
      (node (ref "JP14") (pin "11") (pinfunction "11_11") (pintype "passive"))
    )
    (net (code "132") (name "unconnected-(JP14-Pad12)") (class "Default")
      (node (ref "JP14") (pin "12") (pinfunction "12_12") (pintype "passive"))
    )
    (net (code "133") (name "unconnected-(JP14-Pad13)") (class "Default")
      (node (ref "JP14") (pin "13") (pinfunction "13_13") (pintype "passive"))
    )
    (net (code "134") (name "unconnected-(JP14-Pad14)") (class "Default")
      (node (ref "JP14") (pin "14") (pinfunction "14_14") (pintype "passive"))
    )
    (net (code "135") (name "unconnected-(JP14-Pad15)") (class "Default")
      (node (ref "JP14") (pin "15") (pinfunction "15_15") (pintype "passive"))
    )
    (net (code "136") (name "unconnected-(JP14-Pad16)") (class "Default")
      (node (ref "JP14") (pin "16") (pinfunction "16_16") (pintype "passive"))
    )
    (net (code "137") (name "unconnected-(JP15-Pad1)") (class "Default")
      (node (ref "JP15") (pin "1") (pinfunction "1_1") (pintype "passive"))
    )
    (net (code "138") (name "unconnected-(JP15-Pad2)") (class "Default")
      (node (ref "JP15") (pin "2") (pinfunction "2_2") (pintype "passive"))
    )
    (net (code "139") (name "unconnected-(JP15-Pad3)") (class "Default")
      (node (ref "JP15") (pin "3") (pinfunction "3_3") (pintype "passive"))
    )
    (net (code "140") (name "unconnected-(JP15-Pad4)") (class "Default")
      (node (ref "JP15") (pin "4") (pinfunction "4_4") (pintype "passive"))
    )
    (net (code "141") (name "unconnected-(JP15-Pad5)") (class "Default")
      (node (ref "JP15") (pin "5") (pinfunction "5_5") (pintype "passive"))
    )
    (net (code "142") (name "unconnected-(JP15-Pad6)") (class "Default")
      (node (ref "JP15") (pin "6") (pinfunction "6_6") (pintype "passive"))
    )
    (net (code "143") (name "unconnected-(JP15-Pad7)") (class "Default")
      (node (ref "JP15") (pin "7") (pinfunction "7_7") (pintype "passive"))
    )
    (net (code "144") (name "unconnected-(JP15-Pad8)") (class "Default")
      (node (ref "JP15") (pin "8") (pinfunction "8_8") (pintype "passive"))
    )
    (net (code "145") (name "unconnected-(JP15-Pad9)") (class "Default")
      (node (ref "JP15") (pin "9") (pinfunction "9_9") (pintype "passive"))
    )
    (net (code "146") (name "unconnected-(JP15-Pad10)") (class "Default")
      (node (ref "JP15") (pin "10") (pinfunction "10_10") (pintype "passive"))
    )
    (net (code "147") (name "unconnected-(JP15-Pad11)") (class "Default")
      (node (ref "JP15") (pin "11") (pinfunction "11_11") (pintype "passive"))
    )
    (net (code "148") (name "unconnected-(JP15-Pad12)") (class "Default")
      (node (ref "JP15") (pin "12") (pinfunction "12_12") (pintype "passive"))
    )
    (net (code "149") (name "unconnected-(JP15-Pad13)") (class "Default")
      (node (ref "JP15") (pin "13") (pinfunction "13_13") (pintype "passive"))
    )
    (net (code "150") (name "unconnected-(JP15-Pad14)") (class "Default")
      (node (ref "JP15") (pin "14") (pinfunction "14_14") (pintype "passive"))
    )
    (net (code "151") (name "unconnected-(JP15-Pad15)") (class "Default")
      (node (ref "JP15") (pin "15") (pinfunction "15_15") (pintype "passive"))
    )
    (net (code "152") (name "unconnected-(JP15-Pad16)") (class "Default")
      (node (ref "JP15") (pin "16") (pinfunction "16_16") (pintype "passive"))
    )
    (net (code "153") (name "unconnected-(JP16-Pad1)") (class "Default")
      (node (ref "JP16") (pin "1") (pinfunction "1_1") (pintype "passive"))
    )
    (net (code "154") (name "unconnected-(JP16-Pad2)") (class "Default")
      (node (ref "JP16") (pin "2") (pinfunction "2_2") (pintype "passive"))
    )
    (net (code "155") (name "unconnected-(JP16-Pad3)") (class "Default")
      (node (ref "JP16") (pin "3") (pinfunction "3_3") (pintype "passive"))
    )
    (net (code "156") (name "unconnected-(JP16-Pad4)") (class "Default")
      (node (ref "JP16") (pin "4") (pinfunction "4_4") (pintype "passive"))
    )
    (net (code "157") (name "unconnected-(JP16-Pad5)") (class "Default")
      (node (ref "JP16") (pin "5") (pinfunction "5_5") (pintype "passive"))
    )
    (net (code "158") (name "unconnected-(JP16-Pad6)") (class "Default")
      (node (ref "JP16") (pin "6") (pinfunction "6_6") (pintype "passive"))
    )
    (net (code "159") (name "unconnected-(JP16-Pad7)") (class "Default")
      (node (ref "JP16") (pin "7") (pinfunction "7_7") (pintype "passive"))
    )
    (net (code "160") (name "unconnected-(JP16-Pad8)") (class "Default")
      (node (ref "JP16") (pin "8") (pinfunction "8_8") (pintype "passive"))
    )
    (net (code "161") (name "unconnected-(JP16-Pad9)") (class "Default")
      (node (ref "JP16") (pin "9") (pinfunction "9_9") (pintype "passive"))
    )
    (net (code "162") (name "unconnected-(JP16-Pad10)") (class "Default")
      (node (ref "JP16") (pin "10") (pinfunction "10_10") (pintype "passive"))
    )
    (net (code "163") (name "unconnected-(JP17-Pad1)") (class "Default")
      (node (ref "JP17") (pin "1") (pinfunction "1_1") (pintype "passive"))
    )
    (net (code "164") (name "unconnected-(JP17-Pad2)") (class "Default")
      (node (ref "JP17") (pin "2") (pinfunction "2_2") (pintype "passive"))
    )
    (net (code "165") (name "unconnected-(JP17-Pad3)") (class "Default")
      (node (ref "JP17") (pin "3") (pinfunction "3_3") (pintype "passive"))
    )
    (net (code "166") (name "unconnected-(JP17-Pad4)") (class "Default")
      (node (ref "JP17") (pin "4") (pinfunction "4_4") (pintype "passive"))
    )
    (net (code "167") (name "unconnected-(JP17-Pad5)") (class "Default")
      (node (ref "JP17") (pin "5") (pinfunction "5_5") (pintype "passive"))
    )
    (net (code "168") (name "unconnected-(JP17-Pad6)") (class "Default")
      (node (ref "JP17") (pin "6") (pinfunction "6_6") (pintype "passive"))
    )
    (net (code "169") (name "unconnected-(JP17-Pad7)") (class "Default")
      (node (ref "JP17") (pin "7") (pinfunction "7_7") (pintype "passive"))
    )
    (net (code "170") (name "unconnected-(JP17-Pad8)") (class "Default")
      (node (ref "JP17") (pin "8") (pinfunction "8_8") (pintype "passive"))
    )
    (net (code "171") (name "unconnected-(JP17-Pad9)") (class "Default")
      (node (ref "JP17") (pin "9") (pinfunction "9_9") (pintype "passive"))
    )
    (net (code "172") (name "unconnected-(JP17-Pad10)") (class "Default")
      (node (ref "JP17") (pin "10") (pinfunction "10_10") (pintype "passive"))
    )
    (net (code "173") (name "unconnected-(JP17-Pad11)") (class "Default")
      (node (ref "JP17") (pin "11") (pinfunction "11_11") (pintype "passive"))
    )
    (net (code "174") (name "unconnected-(JP17-Pad12)") (class "Default")
      (node (ref "JP17") (pin "12") (pinfunction "12_12") (pintype "passive"))
    )
    (net (code "175") (name "unconnected-(JP17-Pad13)") (class "Default")
      (node (ref "JP17") (pin "13") (pinfunction "13_13") (pintype "passive"))
    )
    (net (code "176") (name "unconnected-(JP17-Pad14)") (class "Default")
      (node (ref "JP17") (pin "14") (pinfunction "14_14") (pintype "passive"))
    )
    (net (code "177") (name "unconnected-(JP17-Pad15)") (class "Default")
      (node (ref "JP17") (pin "15") (pinfunction "15_15") (pintype "passive"))
    )
    (net (code "178") (name "unconnected-(JP17-Pad16)") (class "Default")
      (node (ref "JP17") (pin "16") (pinfunction "16_16") (pintype "passive"))
    )
    (net (code "179") (name "unconnected-(JP18-Pad1)") (class "Default")
      (node (ref "JP18") (pin "1") (pinfunction "1_1") (pintype "passive"))
    )
    (net (code "180") (name "unconnected-(JP18-Pad2)") (class "Default")
      (node (ref "JP18") (pin "2") (pinfunction "2_2") (pintype "passive"))
    )
    (net (code "181") (name "unconnected-(JP18-Pad3)") (class "Default")
      (node (ref "JP18") (pin "3") (pinfunction "3_3") (pintype "passive"))
    )
    (net (code "182") (name "unconnected-(JP18-Pad4)") (class "Default")
      (node (ref "JP18") (pin "4") (pinfunction "4_4") (pintype "passive"))
    )
    (net (code "183") (name "unconnected-(JP18-Pad5)") (class "Default")
      (node (ref "JP18") (pin "5") (pinfunction "5_5") (pintype "passive"))
    )
    (net (code "184") (name "unconnected-(JP18-Pad6)") (class "Default")
      (node (ref "JP18") (pin "6") (pinfunction "6_6") (pintype "passive"))
    )
    (net (code "185") (name "unconnected-(JP18-Pad7)") (class "Default")
      (node (ref "JP18") (pin "7") (pinfunction "7_7") (pintype "passive"))
    )
    (net (code "186") (name "unconnected-(JP18-Pad8)") (class "Default")
      (node (ref "JP18") (pin "8") (pinfunction "8_8") (pintype "passive"))
    )
    (net (code "187") (name "unconnected-(JP18-Pad9)") (class "Default")
      (node (ref "JP18") (pin "9") (pinfunction "9_9") (pintype "passive"))
    )
    (net (code "188") (name "unconnected-(JP18-Pad10)") (class "Default")
      (node (ref "JP18") (pin "10") (pinfunction "10_10") (pintype "passive"))
    )
    (net (code "189") (name "unconnected-(JP18-Pad11)") (class "Default")
      (node (ref "JP18") (pin "11") (pinfunction "11_11") (pintype "passive"))
    )
    (net (code "190") (name "unconnected-(JP18-Pad12)") (class "Default")
      (node (ref "JP18") (pin "12") (pinfunction "12_12") (pintype "passive"))
    )
    (net (code "191") (name "unconnected-(JP18-Pad13)") (class "Default")
      (node (ref "JP18") (pin "13") (pinfunction "13_13") (pintype "passive"))
    )
    (net (code "192") (name "unconnected-(JP18-Pad14)") (class "Default")
      (node (ref "JP18") (pin "14") (pinfunction "14_14") (pintype "passive"))
    )
    (net (code "193") (name "unconnected-(JP18-Pad15)") (class "Default")
      (node (ref "JP18") (pin "15") (pinfunction "15_15") (pintype "passive"))
    )
    (net (code "194") (name "unconnected-(JP18-Pad16)") (class "Default")
      (node (ref "JP18") (pin "16") (pinfunction "16_16") (pintype "passive"))
    )
    (net (code "195") (name "unconnected-(JP19-Pad1)") (class "Default")
      (node (ref "JP19") (pin "1") (pinfunction "1_1") (pintype "passive"))
    )
    (net (code "196") (name "unconnected-(JP19-Pad2)") (class "Default")
      (node (ref "JP19") (pin "2") (pinfunction "2_2") (pintype "passive"))
    )
    (net (code "197") (name "unconnected-(JP19-Pad3)") (class "Default")
      (node (ref "JP19") (pin "3") (pinfunction "3_3") (pintype "passive"))
    )
    (net (code "198") (name "unconnected-(JP19-Pad4)") (class "Default")
      (node (ref "JP19") (pin "4") (pinfunction "4_4") (pintype "passive"))
    )
    (net (code "199") (name "unconnected-(JP19-Pad5)") (class "Default")
      (node (ref "JP19") (pin "5") (pinfunction "5_5") (pintype "passive"))
    )
    (net (code "200") (name "unconnected-(JP19-Pad6)") (class "Default")
      (node (ref "JP19") (pin "6") (pinfunction "6_6") (pintype "passive"))
    )
    (net (code "201") (name "unconnected-(JP19-Pad7)") (class "Default")
      (node (ref "JP19") (pin "7") (pinfunction "7_7") (pintype "passive"))
    )
    (net (code "202") (name "unconnected-(JP19-Pad8)") (class "Default")
      (node (ref "JP19") (pin "8") (pinfunction "8_8") (pintype "passive"))
    )
    (net (code "203") (name "unconnected-(JP19-Pad9)") (class "Default")
      (node (ref "JP19") (pin "9") (pinfunction "9_9") (pintype "passive"))
    )
    (net (code "204") (name "unconnected-(JP19-Pad10)") (class "Default")
      (node (ref "JP19") (pin "10") (pinfunction "10_10") (pintype "passive"))
    )
    (net (code "205") (name "unconnected-(JP20-Pad1)") (class "Default")
      (node (ref "JP20") (pin "1") (pinfunction "1_1") (pintype "passive"))
    )
    (net (code "206") (name "unconnected-(JP20-Pad2)") (class "Default")
      (node (ref "JP20") (pin "2") (pinfunction "2_2") (pintype "passive"))
    )
    (net (code "207") (name "unconnected-(JP20-Pad3)") (class "Default")
      (node (ref "JP20") (pin "3") (pinfunction "3_3") (pintype "passive"))
    )
    (net (code "208") (name "unconnected-(JP20-Pad4)") (class "Default")
      (node (ref "JP20") (pin "4") (pinfunction "4_4") (pintype "passive"))
    )
    (net (code "209") (name "unconnected-(JP20-Pad5)") (class "Default")
      (node (ref "JP20") (pin "5") (pinfunction "5_5") (pintype "passive"))
    )
    (net (code "210") (name "unconnected-(JP20-Pad6)") (class "Default")
      (node (ref "JP20") (pin "6") (pinfunction "6_6") (pintype "passive"))
    )
    (net (code "211") (name "unconnected-(JP20-Pad7)") (class "Default")
      (node (ref "JP20") (pin "7") (pinfunction "7_7") (pintype "passive"))
    )
    (net (code "212") (name "unconnected-(JP20-Pad8)") (class "Default")
      (node (ref "JP20") (pin "8") (pinfunction "8_8") (pintype "passive"))
    )
    (net (code "213") (name "unconnected-(JP20-Pad9)") (class "Default")
      (node (ref "JP20") (pin "9") (pinfunction "9_9") (pintype "passive"))
    )
    (net (code "214") (name "unconnected-(JP20-Pad10)") (class "Default")
      (node (ref "JP20") (pin "10") (pinfunction "10_10") (pintype "passive"))
    )
    (net (code "215") (name "unconnected-(JP20-Pad11)") (class "Default")
      (node (ref "JP20") (pin "11") (pinfunction "11_11") (pintype "passive"))
    )
    (net (code "216") (name "unconnected-(JP20-Pad12)") (class "Default")
      (node (ref "JP20") (pin "12") (pinfunction "12_12") (pintype "passive"))
    )
    (net (code "217") (name "unconnected-(JP20-Pad13)") (class "Default")
      (node (ref "JP20") (pin "13") (pinfunction "13_13") (pintype "passive"))
    )
    (net (code "218") (name "unconnected-(JP20-Pad14)") (class "Default")
      (node (ref "JP20") (pin "14") (pinfunction "14_14") (pintype "passive"))
    )
    (net (code "219") (name "unconnected-(JP20-Pad15)") (class "Default")
      (node (ref "JP20") (pin "15") (pinfunction "15_15") (pintype "passive"))
    )
    (net (code "220") (name "unconnected-(JP20-Pad16)") (class "Default")
      (node (ref "JP20") (pin "16") (pinfunction "16_16") (pintype "passive"))
    )
    (net (code "221") (name "unconnected-(JP21-Pad1)") (class "Default")
      (node (ref "JP21") (pin "1") (pinfunction "1_1") (pintype "passive"))
    )
    (net (code "222") (name "unconnected-(JP21-Pad2)") (class "Default")
      (node (ref "JP21") (pin "2") (pinfunction "2_2") (pintype "passive"))
    )
    (net (code "223") (name "unconnected-(JP21-Pad3)") (class "Default")
      (node (ref "JP21") (pin "3") (pinfunction "3_3") (pintype "passive"))
    )
    (net (code "224") (name "unconnected-(JP21-Pad4)") (class "Default")
      (node (ref "JP21") (pin "4") (pinfunction "4_4") (pintype "passive"))
    )
    (net (code "225") (name "unconnected-(JP21-Pad5)") (class "Default")
      (node (ref "JP21") (pin "5") (pinfunction "5_5") (pintype "passive"))
    )
    (net (code "226") (name "unconnected-(JP21-Pad6)") (class "Default")
      (node (ref "JP21") (pin "6") (pinfunction "6_6") (pintype "passive"))
    )
    (net (code "227") (name "unconnected-(JP21-Pad7)") (class "Default")
      (node (ref "JP21") (pin "7") (pinfunction "7_7") (pintype "passive"))
    )
    (net (code "228") (name "unconnected-(JP21-Pad8)") (class "Default")
      (node (ref "JP21") (pin "8") (pinfunction "8_8") (pintype "passive"))
    )
    (net (code "229") (name "unconnected-(JP21-Pad9)") (class "Default")
      (node (ref "JP21") (pin "9") (pinfunction "9_9") (pintype "passive"))
    )
    (net (code "230") (name "unconnected-(JP21-Pad10)") (class "Default")
      (node (ref "JP21") (pin "10") (pinfunction "10_10") (pintype "passive"))
    )
    (net (code "231") (name "unconnected-(JP21-Pad11)") (class "Default")
      (node (ref "JP21") (pin "11") (pinfunction "11_11") (pintype "passive"))
    )
    (net (code "232") (name "unconnected-(JP21-Pad12)") (class "Default")
      (node (ref "JP21") (pin "12") (pinfunction "12_12") (pintype "passive"))
    )
    (net (code "233") (name "unconnected-(JP21-Pad13)") (class "Default")
      (node (ref "JP21") (pin "13") (pinfunction "13_13") (pintype "passive"))
    )
    (net (code "234") (name "unconnected-(JP21-Pad14)") (class "Default")
      (node (ref "JP21") (pin "14") (pinfunction "14_14") (pintype "passive"))
    )
    (net (code "235") (name "unconnected-(JP21-Pad15)") (class "Default")
      (node (ref "JP21") (pin "15") (pinfunction "15_15") (pintype "passive"))
    )
    (net (code "236") (name "unconnected-(JP21-Pad16)") (class "Default")
      (node (ref "JP21") (pin "16") (pinfunction "16_16") (pintype "passive"))
    )
    (net (code "237") (name "unconnected-(JP22-Pad1)") (class "Default")
      (node (ref "JP22") (pin "1") (pinfunction "1_1") (pintype "passive"))
    )
    (net (code "238") (name "unconnected-(JP22-Pad2)") (class "Default")
      (node (ref "JP22") (pin "2") (pinfunction "2_2") (pintype "passive"))
    )
    (net (code "239") (name "unconnected-(JP22-Pad3)") (class "Default")
      (node (ref "JP22") (pin "3") (pinfunction "3_3") (pintype "passive"))
    )
    (net (code "240") (name "unconnected-(JP22-Pad4)") (class "Default")
      (node (ref "JP22") (pin "4") (pinfunction "4_4") (pintype "passive"))
    )
    (net (code "241") (name "unconnected-(JP22-Pad5)") (class "Default")
      (node (ref "JP22") (pin "5") (pinfunction "5_5") (pintype "passive"))
    )
    (net (code "242") (name "unconnected-(JP22-Pad6)") (class "Default")
      (node (ref "JP22") (pin "6") (pinfunction "6_6") (pintype "passive"))
    )
    (net (code "243") (name "unconnected-(JP22-Pad7)") (class "Default")
      (node (ref "JP22") (pin "7") (pinfunction "7_7") (pintype "passive"))
    )
    (net (code "244") (name "unconnected-(JP22-Pad8)") (class "Default")
      (node (ref "JP22") (pin "8") (pinfunction "8_8") (pintype "passive"))
    )
    (net (code "245") (name "unconnected-(JP22-Pad9)") (class "Default")
      (node (ref "JP22") (pin "9") (pinfunction "9_9") (pintype "passive"))
    )
    (net (code "246") (name "unconnected-(JP22-Pad10)") (class "Default")
      (node (ref "JP22") (pin "10") (pinfunction "10_10") (pintype "passive"))
    )
    (net (code "247") (name "unconnected-(JP23-Pad1)") (class "Default")
      (node (ref "JP23") (pin "1") (pinfunction "1_1") (pintype "passive"))
    )
    (net (code "248") (name "unconnected-(JP23-Pad2)") (class "Default")
      (node (ref "JP23") (pin "2") (pinfunction "2_2") (pintype "passive"))
    )
    (net (code "249") (name "unconnected-(JP23-Pad3)") (class "Default")
      (node (ref "JP23") (pin "3") (pinfunction "3_3") (pintype "passive"))
    )
    (net (code "250") (name "unconnected-(JP23-Pad4)") (class "Default")
      (node (ref "JP23") (pin "4") (pinfunction "4_4") (pintype "passive"))
    )
    (net (code "251") (name "unconnected-(JP23-Pad5)") (class "Default")
      (node (ref "JP23") (pin "5") (pinfunction "5_5") (pintype "passive"))
    )
    (net (code "252") (name "unconnected-(JP23-Pad6)") (class "Default")
      (node (ref "JP23") (pin "6") (pinfunction "6_6") (pintype "passive"))
    )
    (net (code "253") (name "unconnected-(JP23-Pad7)") (class "Default")
      (node (ref "JP23") (pin "7") (pinfunction "7_7") (pintype "passive"))
    )
    (net (code "254") (name "unconnected-(JP23-Pad8)") (class "Default")
      (node (ref "JP23") (pin "8") (pinfunction "8_8") (pintype "passive"))
    )
    (net (code "255") (name "unconnected-(JP23-Pad9)") (class "Default")
      (node (ref "JP23") (pin "9") (pinfunction "9_9") (pintype "passive"))
    )
    (net (code "256") (name "unconnected-(JP23-Pad10)") (class "Default")
      (node (ref "JP23") (pin "10") (pinfunction "10_10") (pintype "passive"))
    )
    (net (code "257") (name "unconnected-(JP23-Pad11)") (class "Default")
      (node (ref "JP23") (pin "11") (pinfunction "11_11") (pintype "passive"))
    )
    (net (code "258") (name "unconnected-(JP23-Pad12)") (class "Default")
      (node (ref "JP23") (pin "12") (pinfunction "12_12") (pintype "passive"))
    )
    (net (code "259") (name "unconnected-(JP23-Pad13)") (class "Default")
      (node (ref "JP23") (pin "13") (pinfunction "13_13") (pintype "passive"))
    )
    (net (code "260") (name "unconnected-(JP23-Pad14)") (class "Default")
      (node (ref "JP23") (pin "14") (pinfunction "14_14") (pintype "passive"))
    )
    (net (code "261") (name "unconnected-(JP23-Pad15)") (class "Default")
      (node (ref "JP23") (pin "15") (pinfunction "15_15") (pintype "passive"))
    )
    (net (code "262") (name "unconnected-(JP23-Pad16)") (class "Default")
      (node (ref "JP23") (pin "16") (pinfunction "16_16") (pintype "passive"))
    )
    (net (code "263") (name "unconnected-(JP24-Pad1)") (class "Default")
      (node (ref "JP24") (pin "1") (pinfunction "1_1") (pintype "passive"))
    )
    (net (code "264") (name "unconnected-(JP24-Pad2)") (class "Default")
      (node (ref "JP24") (pin "2") (pinfunction "2_2") (pintype "passive"))
    )
    (net (code "265") (name "unconnected-(JP24-Pad3)") (class "Default")
      (node (ref "JP24") (pin "3") (pinfunction "3_3") (pintype "passive"))
    )
    (net (code "266") (name "unconnected-(JP24-Pad4)") (class "Default")
      (node (ref "JP24") (pin "4") (pinfunction "4_4") (pintype "passive"))
    )
    (net (code "267") (name "unconnected-(JP24-Pad5)") (class "Default")
      (node (ref "JP24") (pin "5") (pinfunction "5_5") (pintype "passive"))
    )
    (net (code "268") (name "unconnected-(JP24-Pad6)") (class "Default")
      (node (ref "JP24") (pin "6") (pinfunction "6_6") (pintype "passive"))
    )
    (net (code "269") (name "unconnected-(JP24-Pad7)") (class "Default")
      (node (ref "JP24") (pin "7") (pinfunction "7_7") (pintype "passive"))
    )
    (net (code "270") (name "unconnected-(JP24-Pad8)") (class "Default")
      (node (ref "JP24") (pin "8") (pinfunction "8_8") (pintype "passive"))
    )
    (net (code "271") (name "unconnected-(JP24-Pad9)") (class "Default")
      (node (ref "JP24") (pin "9") (pinfunction "9_9") (pintype "passive"))
    )
    (net (code "272") (name "unconnected-(JP24-Pad10)") (class "Default")
      (node (ref "JP24") (pin "10") (pinfunction "10_10") (pintype "passive"))
    )
    (net (code "273") (name "unconnected-(JP24-Pad11)") (class "Default")
      (node (ref "JP24") (pin "11") (pinfunction "11_11") (pintype "passive"))
    )
    (net (code "274") (name "unconnected-(JP24-Pad12)") (class "Default")
      (node (ref "JP24") (pin "12") (pinfunction "12_12") (pintype "passive"))
    )
    (net (code "275") (name "unconnected-(JP24-Pad13)") (class "Default")
      (node (ref "JP24") (pin "13") (pinfunction "13_13") (pintype "passive"))
    )
    (net (code "276") (name "unconnected-(JP24-Pad14)") (class "Default")
      (node (ref "JP24") (pin "14") (pinfunction "14_14") (pintype "passive"))
    )
    (net (code "277") (name "unconnected-(JP24-Pad15)") (class "Default")
      (node (ref "JP24") (pin "15") (pinfunction "15_15") (pintype "passive"))
    )
    (net (code "278") (name "unconnected-(JP24-Pad16)") (class "Default")
      (node (ref "JP24") (pin "16") (pinfunction "16_16") (pintype "passive"))
    )
  )
)
